# USB_AB.net
KiCad netlist of a schematic drawn in Altium Designer
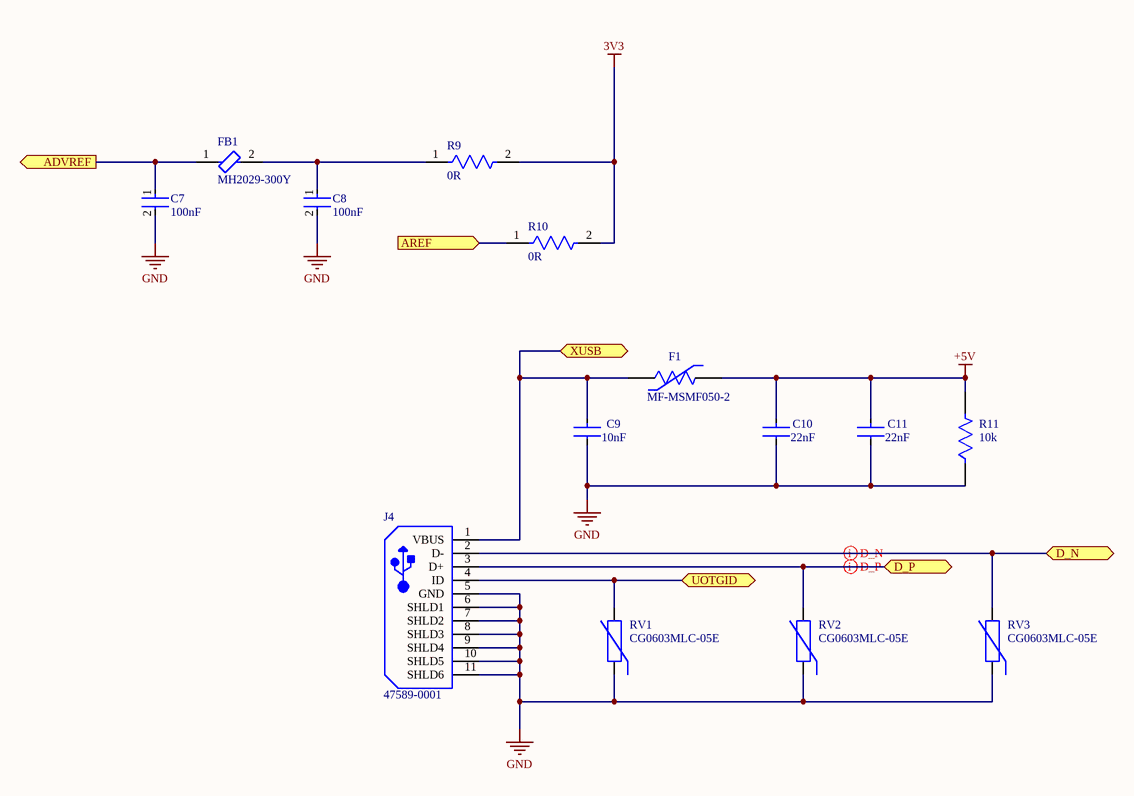
[diagram p0:  USB_AB.SchDoc]

(export (version "E")
  (design (tool "Eeschema 10.0.6"))
  (components
    (comp (ref "C7")
      (value "100nF")
      (footprint "FP-0805-L_2_01_0_2-W_1_25-IPC_B")
      (description "General Purpose Ceramic Capacitor, 0805, 100nF, 10%, X7R, 15%, 100V")
      (fields (field (name "VOLTAGE") "100V") (field (name "TOLERANCE") "10%"))
      (libsource (lib "Altium Content Vault") (part "b4654b650e69147ec39a6b967a45e02"))
    )
    (comp (ref "C8")
      (value "100nF")
      (footprint "FP-0805-L_2_01_0_2-W_1_25-IPC_B")
      (description "General Purpose Ceramic Capacitor, 0805, 100nF, 10%, X7R, 15%, 100V")
      (fields (field (name "VOLTAGE") "100V") (field (name "TOLERANCE") "10%"))
      (libsource (lib "Altium Content Vault") (part "b4654b650e69147ec39a6b967a45e02"))
    )
    (comp (ref "C9")
      (value "10nF")
      (footprint "FP-GRM219-0_1-IPC_B")
      (description "Chip Multilayer Ceramic Capacitors for General Purpose, 0805, 10000pF, C0G, 30ppm/°C, 5%, 50V")
      (fields (field (name "VOLTAGE") "50V") (field (name "TOLERANCE") "5%"))
      (libsource (lib "Altium Content Vault") (part "02cd4be3c70576c341d710602a673aa"))
    )
    (comp (ref "C10")
      (value "22nF")
      (footprint "FP-GRM21B-0_1-IPC_A")
      (description "Chip Multilayer Ceramic Capacitors for General Purpose, 0805, 22000pF, C0G, 30ppm/°C, 5%, 50V")
      (fields (field (name "TOLERANCE") "5%") (field (name "VOLTAGE") "25V"))
      (libsource (lib "") (part "b4654b650e69147ec39a6b967a45e02_1"))
    )
    (comp (ref "C11")
      (value "22nF")
      (footprint "FP-GRM21B-0_1-IPC_A")
      (description "Chip Multilayer Ceramic Capacitors for General Purpose, 0805, 22000pF, C0G, 30ppm/°C, 5%, 50V")
      (fields (field (name "TOLERANCE") "5%") (field (name "VOLTAGE") "25V"))
      (libsource (lib "") (part "b4654b650e69147ec39a6b967a45e02_1"))
    )
    (comp (ref "F1")
      (value "MF-MSMF050-2")
      (footprint "FP-MF-MSMF050-2-MFG")
      (description "PTC RESET FUSE 15V 500MA 1812")
      (fields
        (field (name "MANUFACTURER") "Bourns")
        (field (name "OCTOPART") "https://octopart.com/mf-msmf050-2-bourns-28047")
      )
      (libsource (lib "Altium Content Vault") (part "fc31388045fc42ab786d6d00b506e9f"))
    )
    (comp (ref "FB1")
      (value "MH2029-300Y")
      (footprint "FP-MH2029-MFG")
      (description "FERRITE BEAD 30 OHM 0805 1LN")
      (fields
        (field (name "OCTOPART") "https://octopart.com/mh2029-300y-bourns-756929")
        (field (name "MANUFACTURER") "Bourns")
      )
      (libsource (lib "Altium Content Vault") (part "5f30dd21d616792df468990f7003faa"))
    )
    (comp (ref "J4")
      (value "47589-0001")
      (footprint "MOLX-47589-0001_V")
      (description "Right Angle Female Type AB Micro USB Connector, 30 V, 1.8 A, -30 to 85 degC, RoHS, Tape and Reel")
      (fields (field (name "MANUFACTURER") "Molex"))
      (libsource (lib "Altium Content Vault") (part "USB-5-6SHLD"))
    )
    (comp (ref "R9")
      (value "0R")
      (footprint "FP-CRCW0805-e3-IPC_B")
      (description "RES Thick Film, 0Ω, 0.125W, 0805")
      (libsource (lib "Altium Content Vault") (part "1029c3af85768c4190bb7ad29bc67b5"))
    )
    (comp (ref "R10")
      (value "0R")
      (footprint "FP-CRCW0805-e3-IPC_B")
      (description "RES Thick Film, 0Ω, 0.125W, 0805")
      (libsource (lib "Altium Content Vault") (part "1029c3af85768c4190bb7ad29bc67b5"))
    )
    (comp (ref "R11")
      (value "10k")
      (footprint "FP-CRCW0805-e3-IPC_A")
      (description "RES Thick Film, 10kΩ, 1%, 0.125W, 100ppm/°C, 0805")
      (fields (field (name "TOLERANCE") "1%"))
      (libsource (lib "") (part "1029c3af85768c4190bb7ad29bc67b5_1"))
    )
    (comp (ref "RV1")
      (value "CG0603MLC-05E")
      (footprint "BOUR-CG0603-2_V")
      (description "ESD Protector, 5 V Supply, -40 to 85 degC, 1.6 x 0.8 x 0.55 mm SMD, RoHS, Tape and Reel")
      (fields (field (name "MANUFACTURER") "Bourns"))
      (libsource (lib "Altium Content Vault") (part "BOUR-VSR-2"))
    )
    (comp (ref "RV2")
      (value "CG0603MLC-05E")
      (footprint "BOUR-CG0603-2_V")
      (description "ESD Protector, 5 V Supply, -40 to 85 degC, 1.6 x 0.8 x 0.55 mm SMD, RoHS, Tape and Reel")
      (fields (field (name "MANUFACTURER") "Bourns"))
      (libsource (lib "Altium Content Vault") (part "BOUR-VSR-2"))
    )
    (comp (ref "RV3")
      (value "CG0603MLC-05E")
      (footprint "BOUR-CG0603-2_V")
      (description "ESD Protector, 5 V Supply, -40 to 85 degC, 1.6 x 0.8 x 0.55 mm SMD, RoHS, Tape and Reel")
      (fields (field (name "MANUFACTURER") "Bourns"))
      (libsource (lib "Altium Content Vault") (part "BOUR-VSR-2"))
    )
  )
  (nets
    (net (code "1") (name "+5V") (class "Default")
      (node (ref "C10") (pin "1") (pinfunction "1_1") (pintype "passive"))
      (node (ref "C11") (pin "1") (pinfunction "1_1") (pintype "passive"))
      (node (ref "F1") (pin "2") (pinfunction "2_2") (pintype "passive"))
      (node (ref "R11") (pin "2") (pinfunction "2_2") (pintype "passive"))
    )
    (net (code "2") (name "/ADVREF") (class "Default")
      (node (ref "C7") (pin "1") (pinfunction "1_1") (pintype "passive"))
      (node (ref "FB1") (pin "1") (pinfunction "1_1") (pintype "passive"))
    )
    (net (code "3") (name "/AREF") (class "Default")
      (node (ref "R10") (pin "1") (pinfunction "1_1") (pintype "passive"))
    )
    (net (code "4") (name "/D_N") (class "Default")
      (node (ref "J4") (pin "2") (pinfunction "D-_2") (pintype "passive"))
      (node (ref "RV3") (pin "2") (pinfunction "2_2") (pintype "passive"))
    )
    (net (code "5") (name "/D_P") (class "Default")
      (node (ref "J4") (pin "3") (pinfunction "D+_3") (pintype "passive"))
      (node (ref "RV2") (pin "2") (pinfunction "2_2") (pintype "passive"))
    )
    (net (code "6") (name "/UOTGID") (class "Default")
      (node (ref "J4") (pin "4") (pinfunction "ID_4") (pintype "passive"))
      (node (ref "RV1") (pin "2") (pinfunction "2_2") (pintype "passive"))
    )
    (net (code "7") (name "/XUSB") (class "Default")
      (node (ref "C9") (pin "1") (pinfunction "1_1") (pintype "passive"))
      (node (ref "F1") (pin "1") (pinfunction "1_1") (pintype "passive"))
      (node (ref "J4") (pin "1") (pinfunction "VBUS_1") (pintype "passive"))
    )
    (net (code "8") (name "3V3") (class "Default")
      (node (ref "R10") (pin "2") (pinfunction "2_2") (pintype "passive"))
      (node (ref "R9") (pin "2") (pinfunction "2_2") (pintype "passive"))
    )
    (net (code "9") (name "GND") (class "Default")
      (node (ref "C10") (pin "2") (pinfunction "2_2") (pintype "passive"))
      (node (ref "C11") (pin "2") (pinfunction "2_2") (pintype "passive"))
      (node (ref "C7") (pin "2") (pinfunction "2_2") (pintype "passive"))
      (node (ref "C8") (pin "2") (pinfunction "2_2") (pintype "passive"))
      (node (ref "C9") (pin "2") (pinfunction "2_2") (pintype "passive"))
      (node (ref "J4") (pin "10") (pinfunction "SHLD5_10") (pintype "passive"))
      (node (ref "J4") (pin "11") (pinfunction "SHLD6_11") (pintype "passive"))
      (node (ref "J4") (pin "5") (pinfunction "GND_5") (pintype "passive"))
      (node (ref "J4") (pin "6") (pinfunction "SHLD1_6") (pintype "passive"))
      (node (ref "J4") (pin "7") (pinfunction "SHLD2_7") (pintype "passive"))
      (node (ref "J4") (pin "8") (pinfunction "SHLD3_8") (pintype "passive"))
      (node (ref "J4") (pin "9") (pinfunction "SHLD4_9") (pintype "passive"))
      (node (ref "R11") (pin "1") (pinfunction "1_1") (pintype "passive"))
      (node (ref "RV1") (pin "1") (pinfunction "1_1") (pintype "passive"))
      (node (ref "RV2") (pin "1") (pinfunction "1_1") (pintype "passive"))
      (node (ref "RV3") (pin "1") (pinfunction "1_1") (pintype "passive"))
    )
    (net (code "10") (name "Net-(C8-Pad1)") (class "Default")
      (node (ref "C8") (pin "1") (pinfunction "1_1") (pintype "passive"))
      (node (ref "FB1") (pin "2") (pinfunction "2_2") (pintype "passive"))
      (node (ref "R9") (pin "1") (pinfunction "1_1") (pintype "passive"))
    )
  )
)
